# Power.net
KiCad netlist of a schematic drawn in Altium Designer
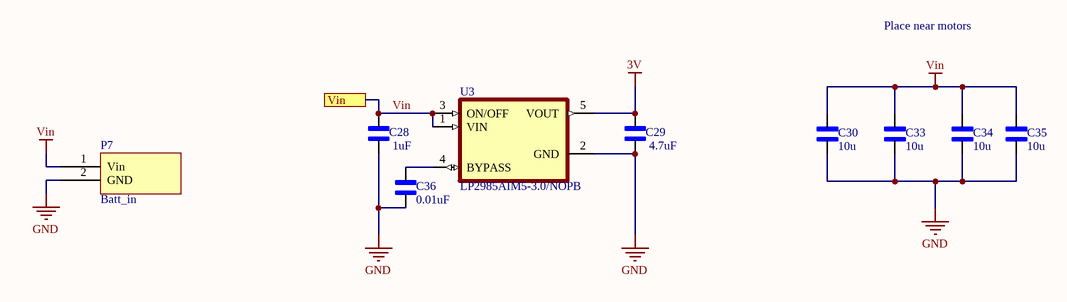
[diagram p0: Power.SchDoc]

(export (version "E")
  (design (tool "Eeschema 10.0.6"))
  (components
    (comp (ref "C28")
      (value "1uF")
      (footprint "0402 Capacitor Generic")
      (description "Generic 0402 Ceramic Capacitor")
      (fields (field (name "MP") "AC0402FR-071ML") (field (name "MF") "Yageo"))
      (libsource (lib "2Ch_Micro_Plane_lib") (part "0402 Ceramic Capacitor"))
    )
    (comp (ref "C29")
      (value "4.7uF")
      (footprint "0402 Capacitor Generic")
      (description "Generic 0402 Ceramic Capacitor")
      (fields (field (name "MP") "AC0402FR-071ML") (field (name "MF") "Yageo"))
      (libsource (lib "2Ch_Micro_Plane_lib") (part "0402 Ceramic Capacitor"))
    )
    (comp (ref "C30")
      (value "10u")
      (footprint "0402 Capacitor Generic")
      (description "Generic 0402 Ceramic Capacitor")
      (fields (field (name "MP") "AC0402FR-071ML") (field (name "MF") "Yageo"))
      (libsource (lib "2Ch_Micro_Plane_lib") (part "0402 Ceramic Capacitor"))
    )
    (comp (ref "C33")
      (value "10u")
      (footprint "0402 Capacitor Generic")
      (description "Generic 0402 Ceramic Capacitor")
      (fields (field (name "MP") "AC0402FR-071ML") (field (name "MF") "Yageo"))
      (libsource (lib "2Ch_Micro_Plane_lib") (part "0402 Ceramic Capacitor"))
    )
    (comp (ref "C34")
      (value "10u")
      (footprint "0402 Capacitor Generic")
      (description "Generic 0402 Ceramic Capacitor")
      (fields (field (name "MP") "AC0402FR-071ML") (field (name "MF") "Yageo"))
      (libsource (lib "2Ch_Micro_Plane_lib") (part "0402 Ceramic Capacitor"))
    )
    (comp (ref "C35")
      (value "10u")
      (footprint "0402 Capacitor Generic")
      (description "Generic 0402 Ceramic Capacitor")
      (fields (field (name "MP") "AC0402FR-071ML") (field (name "MF") "Yageo"))
      (libsource (lib "2Ch_Micro_Plane_lib") (part "0402 Ceramic Capacitor"))
    )
    (comp (ref "C36")
      (value "0.01uF")
      (footprint "0402 Capacitor Generic")
      (description "Generic 0402 Ceramic Capacitor")
      (fields (field (name "MP") "AC0402FR-071ML") (field (name "MF") "Yageo"))
      (libsource (lib "") (part "0402 Ceramic Capacitor_1"))
    )
    (comp (ref "P7")
      (value "Batt_in")
      (footprint "2 Solder Pads")
      (libsource (lib "2Ch_Micro_Plane_lib") (part "Batt_in"))
    )
    (comp (ref "U3")
      (value "LP2985AIM5-3.0/NOPB")
      (footprint "SOT-23")
      (description "Fixed 3V LDO (16V MAX) 150mA SOT-23-5 Linear Voltage Regulator")
      (libsource (lib "2Ch_Micro_Plane_lib") (part "LP2985AIM5-3.0/NOPB"))
    )
  )
  (nets
    (net (code "1") (name "3V") (class "Default")
      (node (ref "C29") (pin "1") (pinfunction "1_1") (pintype "passive"))
      (node (ref "U3") (pin "5") (pinfunction "VOUT_5") (pintype "output"))
    )
    (net (code "2") (name "GND") (class "Default")
      (node (ref "C28") (pin "2") (pinfunction "2_2") (pintype "passive"))
      (node (ref "C29") (pin "2") (pinfunction "2_2") (pintype "passive"))
      (node (ref "C30") (pin "2") (pinfunction "2_2") (pintype "passive"))
      (node (ref "C33") (pin "2") (pinfunction "2_2") (pintype "passive"))
      (node (ref "C34") (pin "2") (pinfunction "2_2") (pintype "passive"))
      (node (ref "C35") (pin "2") (pinfunction "2_2") (pintype "passive"))
      (node (ref "C36") (pin "1") (pinfunction "1_1") (pintype "passive"))
      (node (ref "P7") (pin "2") (pinfunction "GND_2") (pintype "passive"))
      (node (ref "U3") (pin "2") (pinfunction "GND_2") (pintype "power_in"))
    )
    (net (code "3") (name "Net-(U3-BYPASS)") (class "Default")
      (node (ref "C36") (pin "2") (pinfunction "2_2") (pintype "passive"))
      (node (ref "U3") (pin "4") (pinfunction "BYPASS_4") (pintype "bidirectional"))
    )
    (net (code "4") (name "Vin") (class "Default")
      (node (ref "C28") (pin "1") (pinfunction "1_1") (pintype "passive"))
      (node (ref "C30") (pin "1") (pinfunction "1_1") (pintype "passive"))
      (node (ref "C33") (pin "1") (pinfunction "1_1") (pintype "passive"))
      (node (ref "C34") (pin "1") (pinfunction "1_1") (pintype "passive"))
      (node (ref "C35") (pin "1") (pinfunction "1_1") (pintype "passive"))
      (node (ref "P7") (pin "1") (pinfunction "Vin_1") (pintype "passive"))
      (node (ref "U3") (pin "1") (pinfunction "VIN_1") (pintype "input"))
      (node (ref "U3") (pin "3") (pinfunction "ON/OFF_3") (pintype "input"))
    )
  )
)
